# mistral_rtc_candidate0.net
KiCad netlist of a schematic drawn in EAGLE
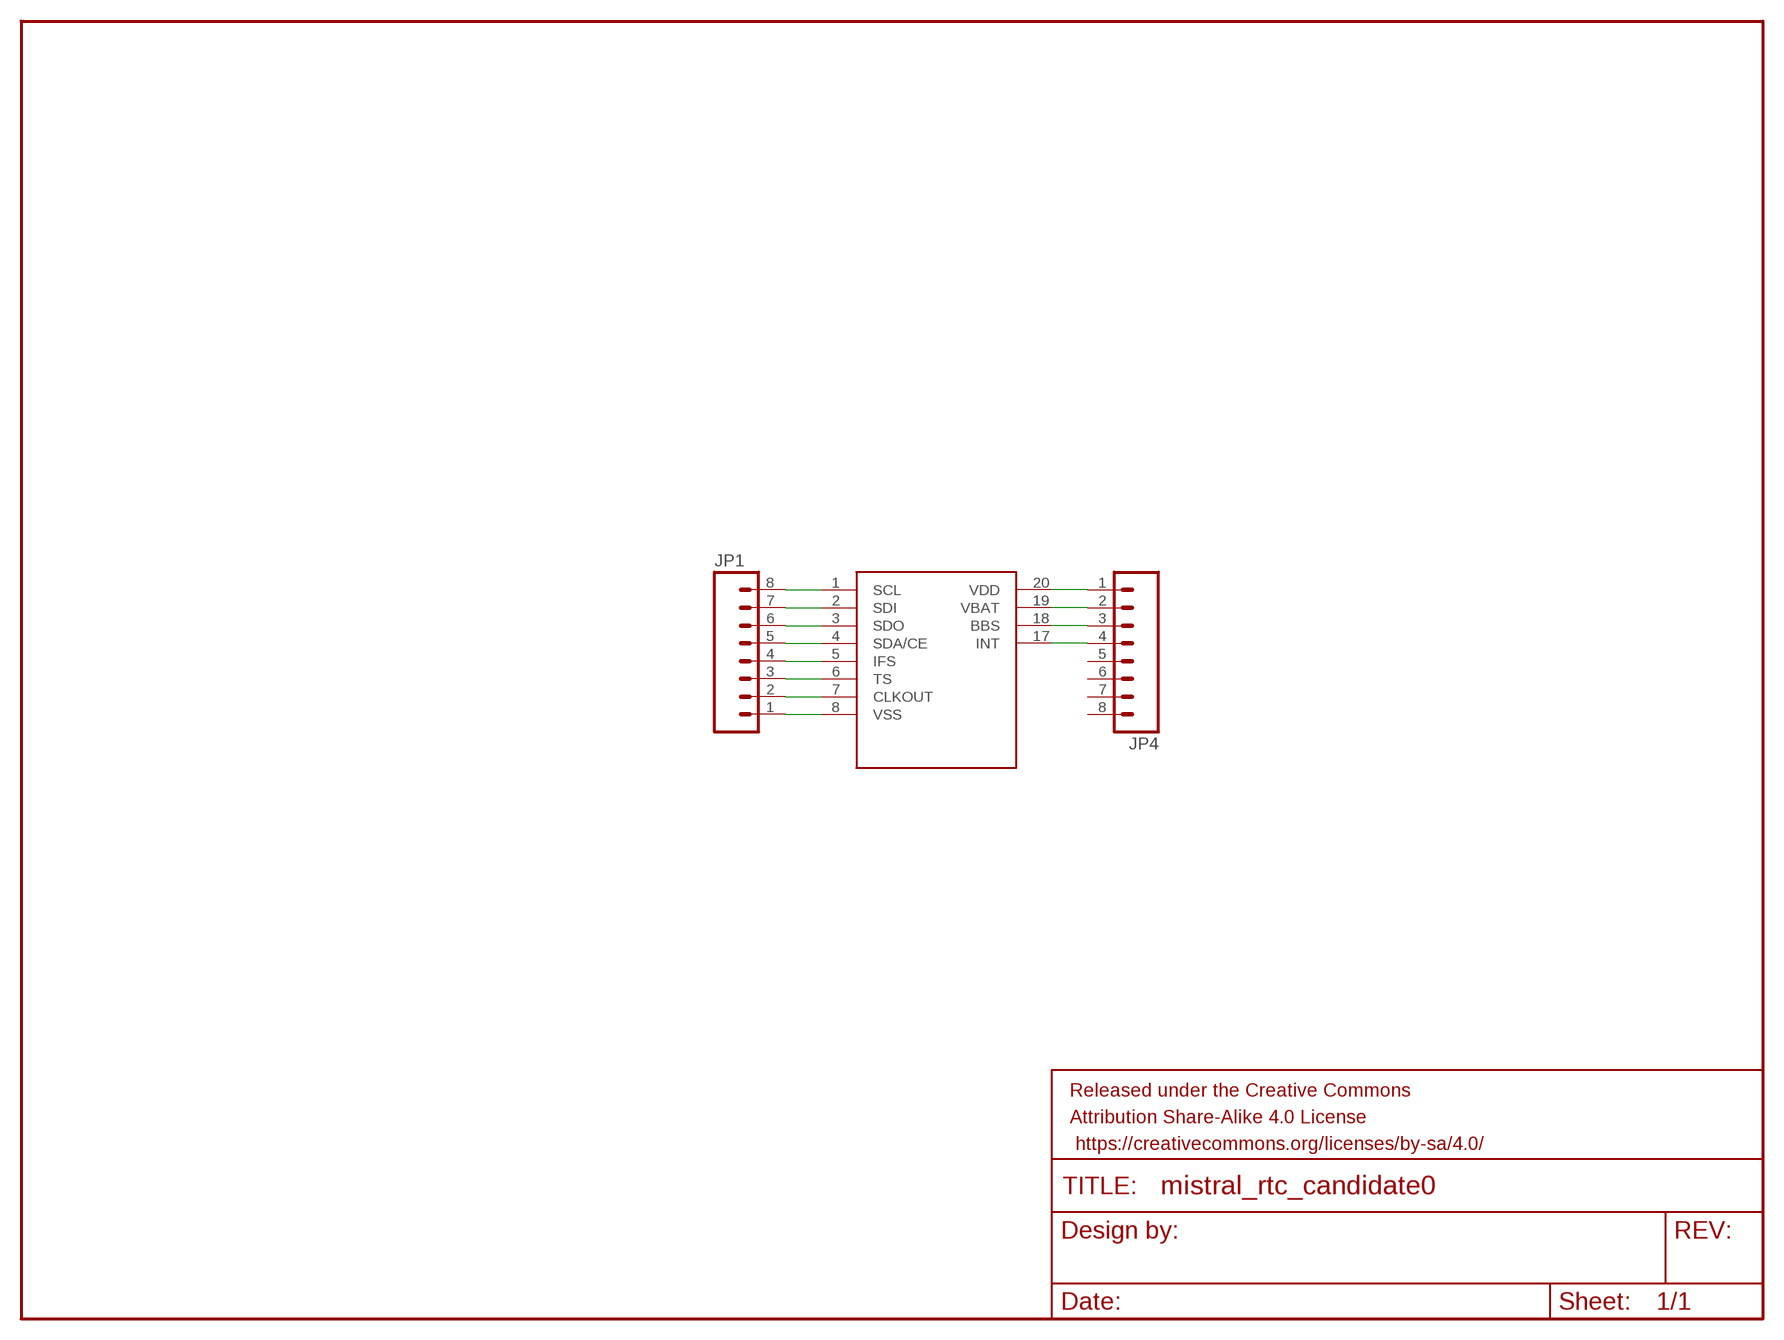
[diagram p0: schematic, sheet 1]

(export (version "E")
  (design (tool "Eeschema 10.0.6"))
  (components
    (comp (ref "FRAME1")
      (value "FRAME-LETTER")
      (footprint "eagle-import:CREATIVE_COMMONS")
      (libsource (lib "eagle-import") (part "FRAME-LETTER"))
    )
    (comp (ref "JP1")
      (value "M08SILK_FEMALE_PTH")
      (footprint "eagle-import:1X08")
      (libsource (lib "eagle-import") (part "M08SILK_FEMALE_PTH"))
    )
    (comp (ref "JP4")
      (value "M08SILK_FEMALE_PTH")
      (footprint "eagle-import:1X08")
      (libsource (lib "eagle-import") (part "M08SILK_FEMALE_PTH"))
    )
    (comp (ref "U$1")
      (value "PCF2129")
      (footprint "eagle-import:PCF2129")
      (libsource (lib "eagle-import") (part "PCF2129"))
    )
  )
  (nets
    (net (code "1") (name "Net-(U$1-BBS)") (class "Default")
      (node (ref "JP4") (pin "3") (pinfunction "3_3") (pintype "passive"))
      (node (ref "U$1") (pin "18") (pinfunction "BBS_18") (pintype "bidirectional"))
    )
    (net (code "2") (name "Net-(U$1-CLKOUT)") (class "Default")
      (node (ref "JP1") (pin "2") (pinfunction "2_2") (pintype "passive"))
      (node (ref "U$1") (pin "7") (pinfunction "CLKOUT_7") (pintype "bidirectional"))
    )
    (net (code "3") (name "Net-(U$1-IFS)") (class "Default")
      (node (ref "JP1") (pin "4") (pinfunction "4_4") (pintype "passive"))
      (node (ref "U$1") (pin "5") (pinfunction "IFS_5") (pintype "bidirectional"))
    )
    (net (code "4") (name "Net-(U$1-INT)") (class "Default")
      (node (ref "JP4") (pin "4") (pinfunction "4_4") (pintype "passive"))
      (node (ref "U$1") (pin "17") (pinfunction "INT_17") (pintype "bidirectional"))
    )
    (net (code "5") (name "Net-(U$1-SCL)") (class "Default")
      (node (ref "JP1") (pin "8") (pinfunction "8_8") (pintype "passive"))
      (node (ref "U$1") (pin "1") (pinfunction "SCL_1") (pintype "bidirectional"))
    )
    (net (code "6") (name "Net-(U$1-SDA{slash}CE)") (class "Default")
      (node (ref "JP1") (pin "5") (pinfunction "5_5") (pintype "passive"))
      (node (ref "U$1") (pin "4") (pinfunction "SDA/CE_4") (pintype "bidirectional"))
    )
    (net (code "7") (name "Net-(U$1-SDI)") (class "Default")
      (node (ref "JP1") (pin "7") (pinfunction "7_7") (pintype "passive"))
      (node (ref "U$1") (pin "2") (pinfunction "SDI_2") (pintype "bidirectional"))
    )
    (net (code "8") (name "Net-(U$1-SDO)") (class "Default")
      (node (ref "JP1") (pin "6") (pinfunction "6_6") (pintype "passive"))
      (node (ref "U$1") (pin "3") (pinfunction "SDO_3") (pintype "bidirectional"))
    )
    (net (code "9") (name "Net-(U$1-TS)") (class "Default")
      (node (ref "JP1") (pin "3") (pinfunction "3_3") (pintype "passive"))
      (node (ref "U$1") (pin "6") (pinfunction "TS_6") (pintype "bidirectional"))
    )
    (net (code "10") (name "Net-(U$1-VBAT)") (class "Default")
      (node (ref "JP4") (pin "2") (pinfunction "2_2") (pintype "passive"))
      (node (ref "U$1") (pin "19") (pinfunction "VBAT_19") (pintype "bidirectional"))
    )
    (net (code "11") (name "Net-(U$1-VDD)") (class "Default")
      (node (ref "JP4") (pin "1") (pinfunction "1_1") (pintype "passive"))
      (node (ref "U$1") (pin "20") (pinfunction "VDD_20") (pintype "bidirectional"))
    )
    (net (code "12") (name "Net-(U$1-VSS)") (class "Default")
      (node (ref "JP1") (pin "1") (pinfunction "1_1") (pintype "passive"))
      (node (ref "U$1") (pin "8") (pinfunction "VSS_8") (pintype "bidirectional"))
    )
    (net (code "13") (name "unconnected-(JP4-Pad5)") (class "Default")
      (node (ref "JP4") (pin "5") (pinfunction "5_5") (pintype "passive"))
    )
    (net (code "14") (name "unconnected-(JP4-Pad6)") (class "Default")
      (node (ref "JP4") (pin "6") (pinfunction "6_6") (pintype "passive"))
    )
    (net (code "15") (name "unconnected-(JP4-Pad7)") (class "Default")
      (node (ref "JP4") (pin "7") (pinfunction "7_7") (pintype "passive"))
    )
    (net (code "16") (name "unconnected-(JP4-Pad8)") (class "Default")
      (node (ref "JP4") (pin "8") (pinfunction "8_8") (pintype "passive"))
    )
  )
)
